# MCU036A_Target_Device.net
KiCad netlist of a schematic drawn in Altium Designer
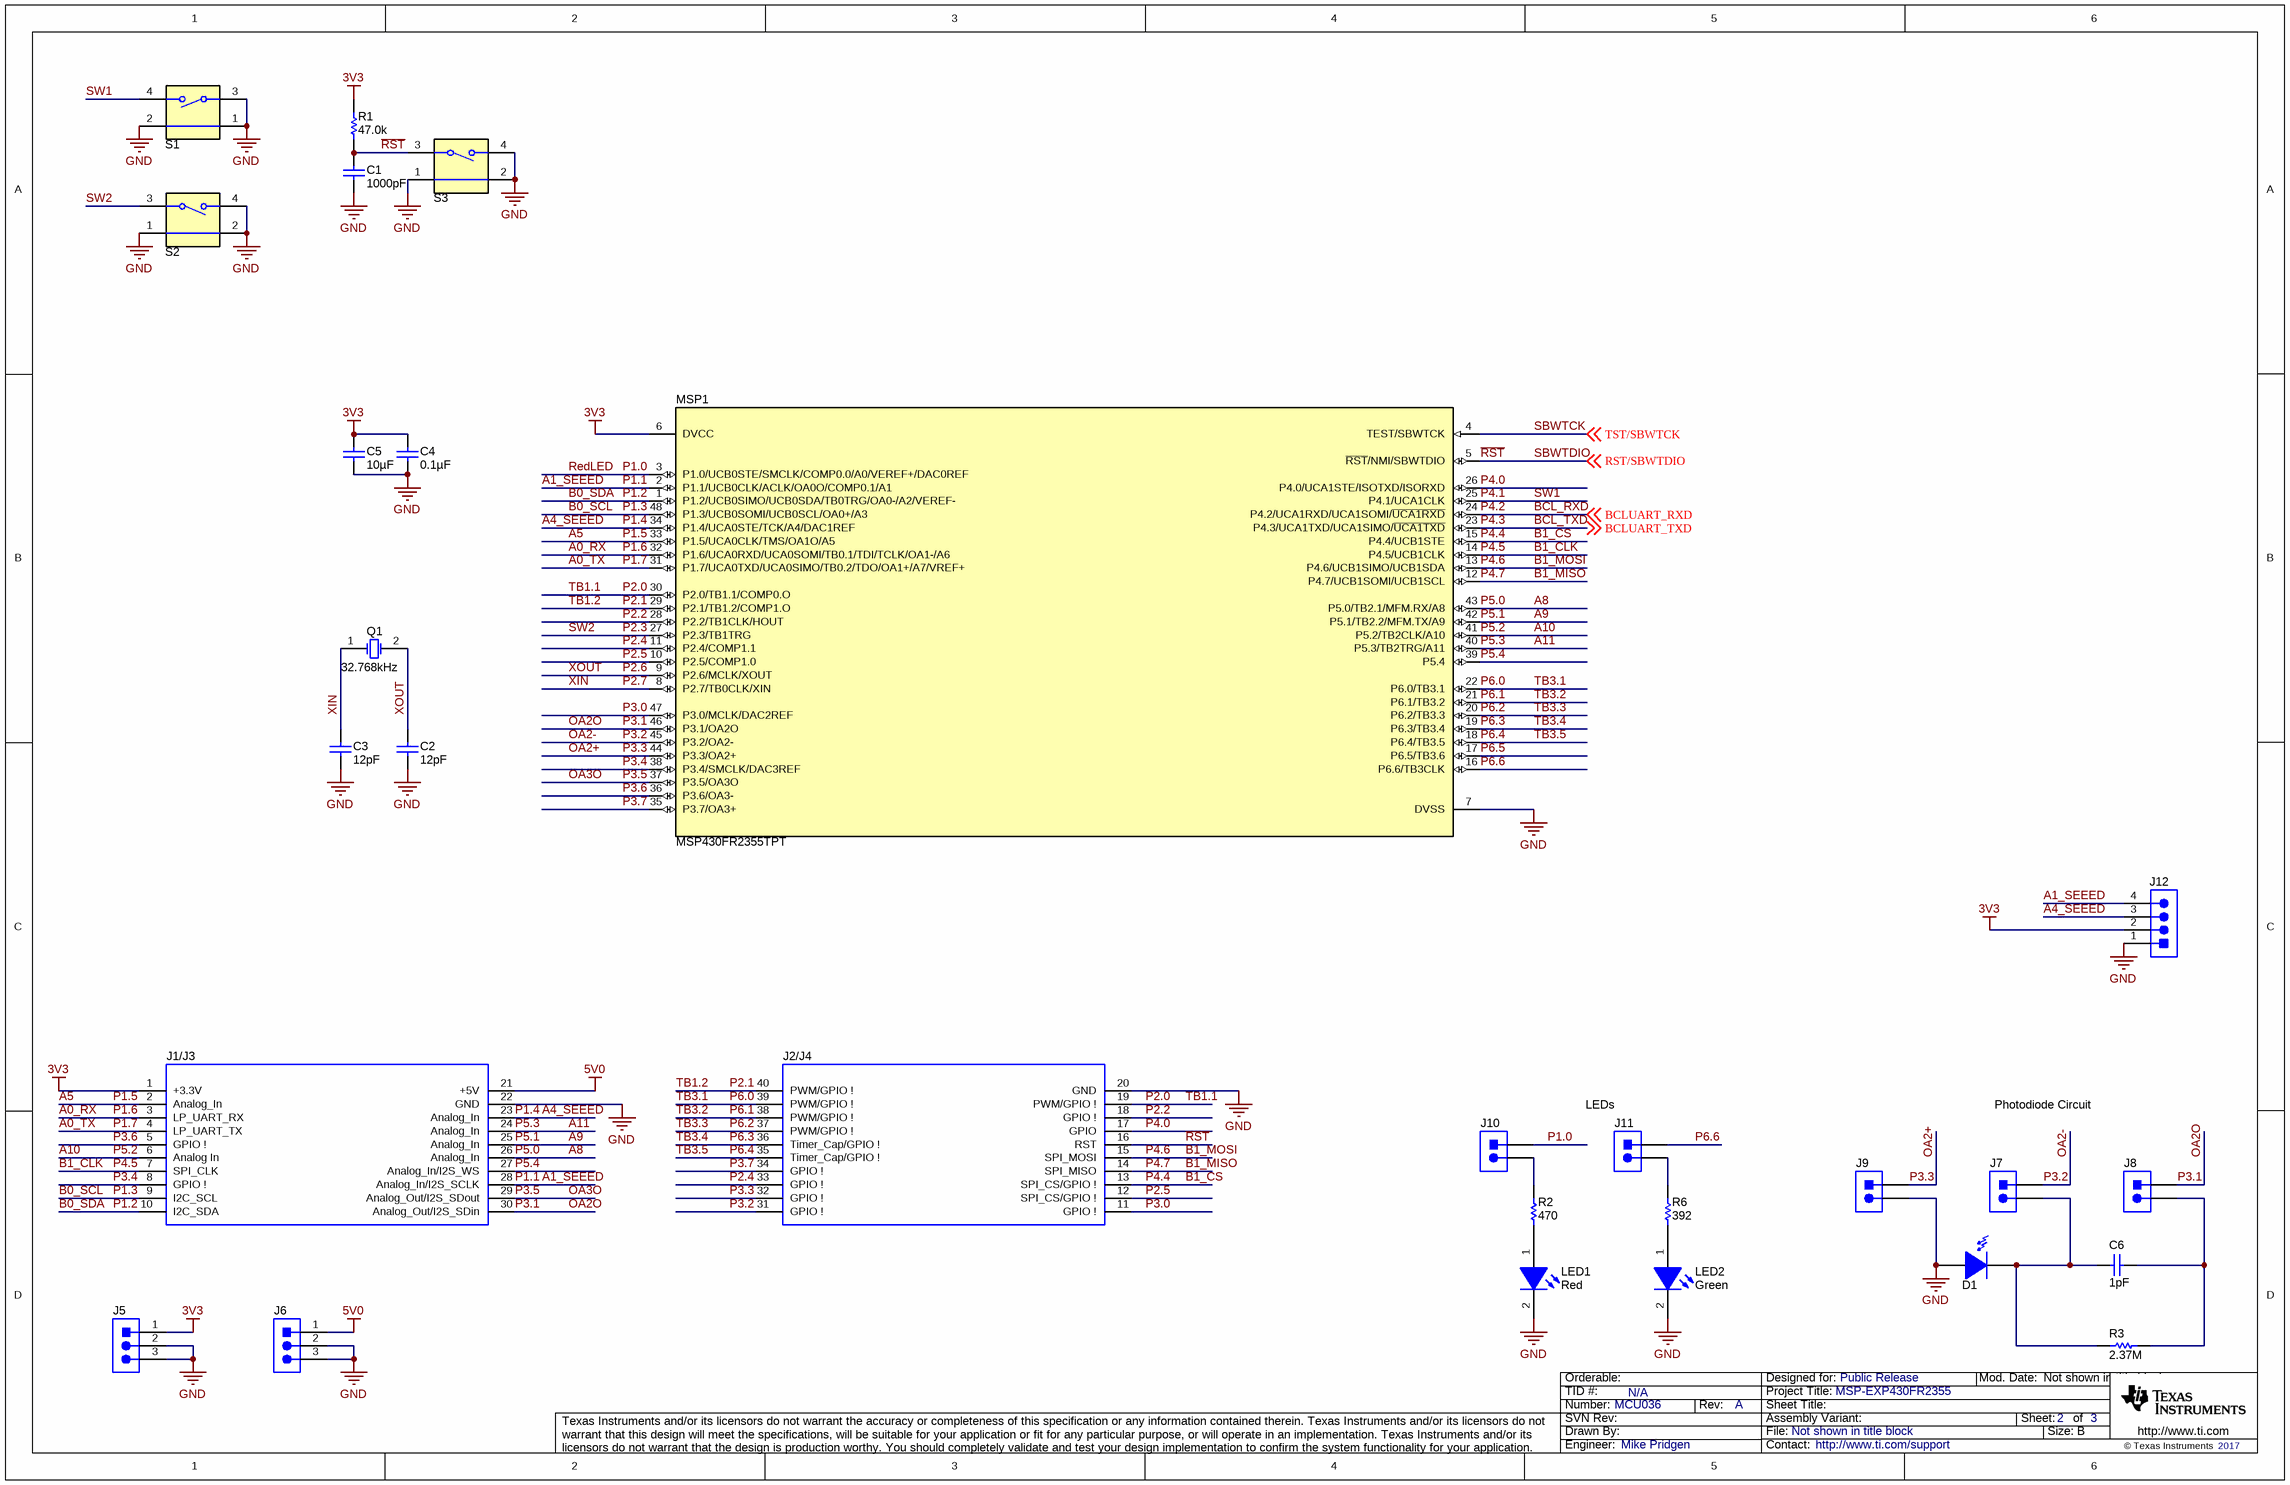
[diagram p0: MCU036A_Target_Device.SchDoc]

(export (version "E")
  (design (tool "Eeschema 10.0.6"))
  (components
    (comp (ref "C1")
      (value "GRM155R71H102KA01D")
      (footprint "0402")
      (description "CAP, CERM, 1000 pF, 50 V, +/- 10%, X7R, 0402")
      (fields
        (field (name "VALUEDISPLAYED") "1000pF")
        (field (name "MANUFACTURER") "MuRata")
        (field (name "PUBLISHER") "Texas Instruments")
      )
      (libsource (lib "Capacitor_Ceramic") (part "GRM155R71H102KA01D"))
    )
    (comp (ref "C2")
      (value "GRM1555C1E120JA01D")
      (footprint "0402")
      (description "CAP, CERM, 12 pF, 25 V, +/- 5%, C0G/NP0, 0402")
      (fields
        (field (name "VALUEDISPLAYED") "12pF")
        (field (name "MANUFACTURER") "MuRata")
        (field (name "PUBLISHER") "Texas Instruments")
      )
      (libsource (lib "Capacitor_Ceramic") (part "GRM1555C1E120JA01D"))
    )
    (comp (ref "C3")
      (value "GRM1555C1E120JA01D")
      (footprint "0402")
      (description "CAP, CERM, 12 pF, 25 V, +/- 5%, C0G/NP0, 0402")
      (fields
        (field (name "VALUEDISPLAYED") "12pF")
        (field (name "MANUFACTURER") "MuRata")
        (field (name "PUBLISHER") "Texas Instruments")
      )
      (libsource (lib "Capacitor_Ceramic") (part "GRM1555C1E120JA01D"))
    )
    (comp (ref "C4")
      (value "GRM155R61H104ME14D")
      (footprint "0402")
      (description "CAP, CERM, 0.1 µF, 50 V, +/- 20%, X5R, 0402")
      (fields
        (field (name "VALUEDISPLAYED") "0.1µF")
        (field (name "MANUFACTURER") "MuRata")
        (field (name "PUBLISHER") "Texas Instruments")
      )
      (libsource (lib "Capacitor_Ceramic") (part "GRM155R61H104ME14D"))
    )
    (comp (ref "C5")
      (value "GRM188R60J106ME84")
      (footprint "0603")
      (description "CAP, CERM, 10 µF, 6.3 V, +/- 20%, X5R, 0603")
      (fields
        (field (name "VALUEDISPLAYED") "10µF")
        (field (name "MANUFACTURER") "MuRata")
        (field (name "PUBLISHER") "Texas Instruments")
      )
      (libsource (lib "Capacitor_Ceramic") (part "GRM188R60J106ME84"))
    )
    (comp (ref "C6")
      (value "GRM1555C1H1R0BA01D")
      (footprint "0402")
      (description "CAP, CERM, 1 pF, 50 V, +/- 10%, C0G/NP0, 0402")
      (fields
        (field (name "VALUEDISPLAYED") "1pF")
        (field (name "MANUFACTURER") "MuRata")
        (field (name "PUBLISHER") "Texas Instruments")
      )
      (libsource (lib "Capacitor_Ceramic") (part "GRM1555C1H1R0BA01D"))
    )
    (comp (ref "D1")
      (value "SFH 2701")
      (footprint "SFH_2701")
      (description "High Speed PIN Photodiode, SMD")
      (fields (field (name "MANUFACTURER") "OSRAM"))
      (libsource (lib "Altium Vault - TI") (part "CMP-0002013-3"))
    )
    (comp (ref "J1/J3")
      (value "SSQ-110-03-T-D")
      (footprint "BoosterPack_40pin_J1J3")
      (description "Receptacle, 2.54mm, 10x2, Tin, TH")
      (fields
        (field (name "MANUFACTURER") "Samtec")
        (field (name "ALTERNATE PARTNUMBER") "CRD-081413-A-G")
        (field (name "SYMBOLCREATOR") "a0412235")
        (field (name "PUBLISHER") "Texas Instruments")
      )
      (libsource (lib "Hardware") (part "BoosterPack_40pin_J1J3"))
    )
    (comp (ref "J2/J4")
      (value "SSQ-110-03-T-D")
      (footprint "BoosterPack_40pin_J2J4")
      (description "Receptacle, 2.54mm, 10x2, Tin, TH")
      (fields
        (field (name "MANUFACTURER") "Samtec")
        (field (name "ALTERNATE PARTNUMBER") "CRD-081413-A-G")
        (field (name "SYMBOLCREATOR") "a0412235")
        (field (name "PUBLISHER") "Texas Instruments")
      )
      (libsource (lib "Hardware") (part "BoosterPack_40pin_J2J4"))
    )
    (comp (ref "J5")
      (value "PEC03SAAN")
      (footprint "PEC03SAAN_Launchpad_3V3")
      (description "Header, 100mil, 3x1, Tin, TH")
      (fields
        (field (name "MANUFACTURER") "Sullins Connector Solutions")
        (field (name "SYMBOLCREATOR") "a0799628")
        (field (name "PUBLISHER") "Texas Instruments")
      )
      (libsource (lib "Connectors_Sullins") (part "PEC03SAAN"))
    )
    (comp (ref "J6")
      (value "PEC03SAAN")
      (footprint "PEC03SAAN_Launchpad_5V0")
      (description "Header, 100mil, 3x1, Tin, TH")
      (fields
        (field (name "MANUFACTURER") "Sullins Connector Solutions")
        (field (name "SYMBOLCREATOR") "a0799628")
        (field (name "PUBLISHER") "Texas Instruments")
      )
      (libsource (lib "Connectors_Sullins") (part "PEC03SAAN"))
    )
    (comp (ref "J7")
      (value "TSW-102-07-G-S")
      (footprint "TSW-102-07-G-S")
      (description "Header, 100mil, 2x1, Gold, TH")
      (fields
        (field (name "MANUFACTURER") "Samtec")
        (field (name "SYMBOLCREATOR") "a0412235")
        (field (name "PUBLISHER") "Texas Instruments")
      )
      (libsource (lib "Connectors_Samtec") (part "TSW-102-07-G-S"))
    )
    (comp (ref "J8")
      (value "TSW-102-07-G-S")
      (footprint "TSW-102-07-G-S")
      (description "Header, 100mil, 2x1, Gold, TH")
      (fields
        (field (name "MANUFACTURER") "Samtec")
        (field (name "SYMBOLCREATOR") "a0412235")
        (field (name "PUBLISHER") "Texas Instruments")
      )
      (libsource (lib "Connectors_Samtec") (part "TSW-102-07-G-S"))
    )
    (comp (ref "J9")
      (value "TSW-102-07-G-S")
      (footprint "TSW-102-07-G-S")
      (description "Header, 100mil, 2x1, Gold, TH")
      (fields
        (field (name "MANUFACTURER") "Samtec")
        (field (name "SYMBOLCREATOR") "a0412235")
        (field (name "PUBLISHER") "Texas Instruments")
      )
      (libsource (lib "Connectors_Samtec") (part "TSW-102-07-G-S"))
    )
    (comp (ref "J10")
      (value "TSW-102-07-G-S")
      (footprint "TSW-102-07-G-S")
      (description "Header, 100mil, 2x1, Gold, TH")
      (fields
        (field (name "MANUFACTURER") "Samtec")
        (field (name "SYMBOLCREATOR") "a0412235")
        (field (name "PUBLISHER") "Texas Instruments")
      )
      (libsource (lib "Connectors_Samtec") (part "TSW-102-07-G-S"))
    )
    (comp (ref "J11")
      (value "TSW-102-07-G-S")
      (footprint "TSW-102-07-G-S")
      (description "Header, 100mil, 2x1, Gold, TH")
      (fields
        (field (name "MANUFACTURER") "Samtec")
        (field (name "SYMBOLCREATOR") "a0412235")
        (field (name "PUBLISHER") "Texas Instruments")
      )
      (libsource (lib "Connectors_Samtec") (part "TSW-102-07-G-S"))
    )
    (comp (ref "J12")
      (value "110990037")
      (footprint "SEEED_110990037")
      (description "Header(shrouded), 2mm, 4x1, Tin, R/A, TH")
      (fields
        (field (name "MANUFACTURER") "SEEED")
        (field (name "SYMBOLCREATOR") "a0412235")
        (field (name "PUBLISHER") "Texas Instruments")
      )
      (libsource (lib "Connectors_Other") (part "110990037"))
    )
    (comp (ref "LED1")
      (value "Red")
      (footprint "LED_LTST-C190_Red")
      (description "LED, Red, SMD")
      (fields
        (field (name "PARTNUMBER") "LTST-C190CKT")
        (field (name "MANUFACTURER") "Lite-On")
        (field (name "PUBLISHER") "Texas Instruments")
      )
      (libsource (lib "LED") (part "LTST-C190CKT"))
    )
    (comp (ref "LED2")
      (value "Green")
      (footprint "LED_LTST-C190")
      (description "LED, Green, SMD")
      (fields
        (field (name "PARTNUMBER") "LTST-C190GKT")
        (field (name "MANUFACTURER") "Lite-On")
        (field (name "PUBLISHER") "Texas Instruments")
      )
      (libsource (lib "LED") (part "LTST-C190GKT"))
    )
    (comp (ref "MSP1")
      (value "MSP430FR2355TPT")
      (footprint "PT0048A_N")
      (description "Mixed-Signal Microcontroller, PT0048A (LQFP-48)")
      (fields
        (field (name "ALTERNATE PARTNUMBER") "XMS430FR2355TPT")
        (field (name "MANUFACTURER") "Texas Instruments")
        (field (name "SYMBOLCREATOR") "Altium")
        (field (name "PUBLISHER") "Texas Instruments")
      )
      (libsource (lib "TI_Pre_RTM") (part "MSP430FR2355IPT"))
    )
    (comp (ref "Q1")
      (value "ECS-.327-12.5-34B-TR")
      (footprint "Epson_FC-135")
      (description "Crystal, 32.768 KHz, 12.5 pF, SMD")
      (fields
        (field (name "FREQUENCY") "32.768kHz")
        (field (name "MANUFACTURER") "ECS Inc.")
        (field (name "SYMBOLCREATOR") "a0412235")
        (field (name "PUBLISHER") "Texas Instruments")
      )
      (libsource (lib "Oscillators") (part "X1A0001410014"))
    )
    (comp (ref "R1")
      (value "RC0402FR-0747KL")
      (footprint "0402")
      (description "RES, 47.0 k, 1%, 0.0625 W, 0402")
      (fields
        (field (name "VALUEDISPLAYED") "47.0k")
        (field (name "MANUFACTURER") "Yageo America")
        (field (name "PUBLISHER") "Texas Instruments")
      )
      (libsource (lib "Resistor_0402") (part "RC0402FR-0747KL"))
    )
    (comp (ref "R2")
      (value "RC0402FR-07470RL")
      (footprint "0402")
      (description "RES, 470, 1%, 0.063 W, 0402")
      (fields
        (field (name "VALUEDISPLAYED") "470")
        (field (name "MANUFACTURER") "Yageo America")
        (field (name "PUBLISHER") "Texas Instruments")
      )
      (libsource (lib "Resistor_0402") (part "RC0402FR-07470RL"))
    )
    (comp (ref "R3")
      (value "CRCW06032M37FKEA")
      (footprint "0603")
      (description "RES, 2.37 M, 1%, 0.1 W, 0603")
      (fields
        (field (name "VALUEDISPLAYED") "2.37M")
        (field (name "MANUFACTURER") "Vishay-Dale")
        (field (name "PUBLISHER") "Texas Instruments")
      )
      (libsource (lib "Resistor_0603") (part "CRCW06032M37FKEA"))
    )
    (comp (ref "R6")
      (value "CRCW0402392RFKED")
      (footprint "0402")
      (description "RES, 392, 1%, 0.063 W, 0402")
      (fields
        (field (name "VALUEDISPLAYED") "392")
        (field (name "MANUFACTURER") "Vishay-Dale")
        (field (name "PUBLISHER") "Texas Instruments")
      )
      (libsource (lib "Resistor_0402") (part "CRCW0402392RFKED"))
    )
    (comp (ref "S1")
      (value "1188E-1K2-V-TR")
      (footprint "SW_1188E")
      (description "Switch, SPST, 0.05 A, 12 VDC, SMD")
      (fields
        (field (name "MANUFACTURER") "Diptronics")
        (field (name "SYMBOLCREATOR") "Altium")
        (field (name "PUBLISHER") "Texas Instruments")
      )
      (libsource (lib "") (part "1188E-1K2-V-TR_1"))
    )
    (comp (ref "S2")
      (value "1188E-1K2-V-TR")
      (footprint "SW_1188E")
      (description "Switch, SPST, 0.05 A, 12 VDC, SMD")
      (fields
        (field (name "MANUFACTURER") "Diptronics")
        (field (name "SYMBOLCREATOR") "Altium")
        (field (name "PUBLISHER") "Texas Instruments")
      )
      (libsource (lib "Switches") (part "1188E-1K2-V-TR"))
    )
    (comp (ref "S3")
      (value "1188E-1K2-V-TR")
      (footprint "SW_1188E")
      (description "Switch, SPST, 0.05 A, 12 VDC, SMD")
      (fields
        (field (name "MANUFACTURER") "Diptronics")
        (field (name "SYMBOLCREATOR") "Altium")
        (field (name "PUBLISHER") "Texas Instruments")
      )
      (libsource (lib "Switches") (part "1188E-1K2-V-TR"))
    )
  )
  (nets
    (net (code "1") (name "/A0_RX") (class "Default")
      (node (ref "J1/J3") (pin "3") (pinfunction "LP_UART_RX_3") (pintype "passive"))
      (node (ref "MSP1") (pin "32") (pinfunction "P1.6/UCA0RXD/UCA0SOMI/TB0.1/TDI/TCLK/OA1-/A6_32") (pintype "bidirectional"))
    )
    (net (code "2") (name "/A0_TX") (class "Default")
      (node (ref "J1/J3") (pin "4") (pinfunction "LP_UART_TX_4") (pintype "passive"))
      (node (ref "MSP1") (pin "31") (pinfunction "P1.7/UCA0TXD/UCA0SIMO/TB0.2/TDO/OA1+/A7/VREF+_31") (pintype "bidirectional"))
    )
    (net (code "3") (name "/A1_SEEED") (class "Default")
      (node (ref "J1/J3") (pin "28") (pinfunction "Analog_In/I2S_SCLK_28") (pintype "passive"))
      (node (ref "J12") (pin "4") (pinfunction "4_4") (pintype "passive"))
      (node (ref "MSP1") (pin "2") (pinfunction "P1.1/UCB0CLK/ACLK/OA0O/COMP0.1/A1_2") (pintype "bidirectional"))
    )
    (net (code "4") (name "/A4_SEEED") (class "Default")
      (node (ref "J1/J3") (pin "23") (pinfunction "Analog_In_23") (pintype "passive"))
      (node (ref "J12") (pin "3") (pinfunction "3_3") (pintype "passive"))
      (node (ref "MSP1") (pin "34") (pinfunction "P1.4/UCA0STE/TCK/A4/DAC1REF_34") (pintype "bidirectional"))
    )
    (net (code "5") (name "/A5") (class "Default")
      (node (ref "J1/J3") (pin "2") (pinfunction "Analog_In_2") (pintype "passive"))
      (node (ref "MSP1") (pin "33") (pinfunction "P1.5/UCA0CLK/TMS/OA1O/A5_33") (pintype "bidirectional"))
    )
    (net (code "6") (name "/A8") (class "Default")
      (node (ref "J1/J3") (pin "26") (pinfunction "Analog_In_26") (pintype "passive"))
      (node (ref "MSP1") (pin "43") (pinfunction "P5.0/TB2.1/MFM.RX/A8_43") (pintype "bidirectional"))
    )
    (net (code "7") (name "/A9") (class "Default")
      (node (ref "J1/J3") (pin "25") (pinfunction "Analog_In_25") (pintype "passive"))
      (node (ref "MSP1") (pin "42") (pinfunction "P5.1/TB2.2/MFM.TX/A9_42") (pintype "bidirectional"))
    )
    (net (code "8") (name "/A10") (class "Default")
      (node (ref "J1/J3") (pin "6") (pinfunction "Analog_In_6") (pintype "passive"))
      (node (ref "MSP1") (pin "41") (pinfunction "P5.2/TB2CLK/A10_41") (pintype "bidirectional"))
    )
    (net (code "9") (name "/A11") (class "Default")
      (node (ref "J1/J3") (pin "24") (pinfunction "Analog_In_24") (pintype "passive"))
      (node (ref "MSP1") (pin "40") (pinfunction "P5.3/TB2TRG/A11_40") (pintype "bidirectional"))
    )
    (net (code "10") (name "/B0_SCL") (class "Default")
      (node (ref "J1/J3") (pin "9") (pinfunction "I2C_SCL_9") (pintype "passive"))
      (node (ref "MSP1") (pin "48") (pinfunction "P1.3/UCB0SOMI/UCB0SCL/OA0+/A3_48") (pintype "bidirectional"))
    )
    (net (code "11") (name "/B0_SDA") (class "Default")
      (node (ref "J1/J3") (pin "10") (pinfunction "I2C_SDA_10") (pintype "passive"))
      (node (ref "MSP1") (pin "1") (pinfunction "P1.2/UCB0SIMO/UCB0SDA/TB0TRG/OA0-/A2/VEREF-_1") (pintype "bidirectional"))
    )
    (net (code "12") (name "/B1_CLK") (class "Default")
      (node (ref "J1/J3") (pin "7") (pinfunction "SPI_CLK_7") (pintype "passive"))
      (node (ref "MSP1") (pin "14") (pinfunction "P4.5/UCB1CLK_14") (pintype "bidirectional"))
    )
    (net (code "13") (name "/B1_CS") (class "Default")
      (node (ref "J2/J4") (pin "13") (pinfunction "SPI_CS/GPIO_!_13") (pintype "passive"))
      (node (ref "MSP1") (pin "15") (pinfunction "P4.4/UCB1STE_15") (pintype "bidirectional"))
    )
    (net (code "14") (name "/B1_MISO") (class "Default")
      (node (ref "J2/J4") (pin "14") (pinfunction "SPI_MISO_14") (pintype "passive"))
      (node (ref "MSP1") (pin "12") (pinfunction "P4.7/UCB1SOMI/UCB1SCL_12") (pintype "bidirectional"))
    )
    (net (code "15") (name "/B1_MOSI") (class "Default")
      (node (ref "J2/J4") (pin "15") (pinfunction "SPI_MOSI_15") (pintype "passive"))
      (node (ref "MSP1") (pin "13") (pinfunction "P4.6/UCB1SIMO/UCB1SDA_13") (pintype "bidirectional"))
    )
    (net (code "16") (name "/OA2+") (class "Default")
      (node (ref "J2/J4") (pin "32") (pinfunction "GPIO_!_32") (pintype "passive"))
      (node (ref "J9") (pin "1") (pinfunction "1_1") (pintype "passive"))
      (node (ref "MSP1") (pin "44") (pinfunction "P3.3/OA2+_44") (pintype "bidirectional"))
    )
    (net (code "17") (name "/OA2-") (class "Default")
      (node (ref "J2/J4") (pin "31") (pinfunction "GPIO_!_31") (pintype "passive"))
      (node (ref "J7") (pin "1") (pinfunction "1_1") (pintype "passive"))
      (node (ref "MSP1") (pin "45") (pinfunction "P3.2/OA2-_45") (pintype "bidirectional"))
    )
    (net (code "18") (name "/OA2O") (class "Default")
      (node (ref "J1/J3") (pin "30") (pinfunction "Analog_Out/I2S_SDin_30") (pintype "passive"))
      (node (ref "J8") (pin "1") (pinfunction "1_1") (pintype "passive"))
      (node (ref "MSP1") (pin "46") (pinfunction "P3.1/OA2O_46") (pintype "bidirectional"))
    )
    (net (code "19") (name "/OA3O") (class "Default")
      (node (ref "J1/J3") (pin "29") (pinfunction "Analog_Out/I2S_SDout_29") (pintype "passive"))
      (node (ref "MSP1") (pin "37") (pinfunction "P3.5/OA3O_37") (pintype "bidirectional"))
    )
    (net (code "20") (name "/P1.0") (class "Default")
      (node (ref "J10") (pin "1") (pinfunction "1_1") (pintype "passive"))
      (node (ref "MSP1") (pin "3") (pinfunction "P1.0/UCB0STE/SMCLK/COMP0.0/A0/VEREF+/DAC0REF_3") (pintype "bidirectional"))
    )
    (net (code "21") (name "/P2.0") (class "Default")
      (node (ref "J2/J4") (pin "19") (pinfunction "PWM/GPIO_!_19") (pintype "passive"))
      (node (ref "MSP1") (pin "30") (pinfunction "P2.0/TB1.1/COMP0.O_30") (pintype "bidirectional"))
    )
    (net (code "22") (name "/P2.1") (class "Default")
      (node (ref "J2/J4") (pin "40") (pinfunction "PWM/GPIO_!_40") (pintype "passive"))
      (node (ref "MSP1") (pin "29") (pinfunction "P2.1/TB1.2/COMP1.O_29") (pintype "bidirectional"))
    )
    (net (code "23") (name "/P2.2") (class "Default")
      (node (ref "J2/J4") (pin "18") (pinfunction "GPIO_!_18") (pintype "passive"))
      (node (ref "MSP1") (pin "28") (pinfunction "P2.2/TB1CLK/HOUT_28") (pintype "bidirectional"))
    )
    (net (code "24") (name "/P2.3") (class "Default")
      (node (ref "MSP1") (pin "27") (pinfunction "P2.3/TB1TRG_27") (pintype "bidirectional"))
      (node (ref "S2") (pin "3") (pinfunction "3_3") (pintype "passive"))
    )
    (net (code "25") (name "/P2.4") (class "Default")
      (node (ref "J2/J4") (pin "33") (pinfunction "GPIO_!_33") (pintype "passive"))
      (node (ref "MSP1") (pin "11") (pinfunction "P2.4/COMP1.1_11") (pintype "bidirectional"))
    )
    (net (code "26") (name "/P2.5") (class "Default")
      (node (ref "J2/J4") (pin "12") (pinfunction "SPI_CS/GPIO_!_12") (pintype "passive"))
      (node (ref "MSP1") (pin "10") (pinfunction "P2.5/COMP1.0_10") (pintype "bidirectional"))
    )
    (net (code "27") (name "/P2.6") (class "Default")
      (node (ref "C2") (pin "1") (pinfunction "1_1") (pintype "passive"))
      (node (ref "MSP1") (pin "9") (pinfunction "P2.6/MCLK/XOUT_9") (pintype "bidirectional"))
      (node (ref "Q1") (pin "2") (pinfunction "OSC2_2") (pintype "passive"))
    )
    (net (code "28") (name "/P2.7") (class "Default")
      (node (ref "C3") (pin "1") (pinfunction "1_1") (pintype "passive"))
      (node (ref "MSP1") (pin "8") (pinfunction "P2.7/TB0CLK/XIN_8") (pintype "bidirectional"))
      (node (ref "Q1") (pin "1") (pinfunction "OSC1_1") (pintype "passive"))
    )
    (net (code "29") (name "/P3.0") (class "Default")
      (node (ref "J2/J4") (pin "11") (pinfunction "GPIO_!_11") (pintype "passive"))
      (node (ref "MSP1") (pin "47") (pinfunction "P3.0/MCLK/DAC2REF_47") (pintype "bidirectional"))
    )
    (net (code "30") (name "/P3.4") (class "Default")
      (node (ref "J1/J3") (pin "8") (pinfunction "GPIO_!_8") (pintype "passive"))
      (node (ref "MSP1") (pin "38") (pinfunction "P3.4/SMCLK/DAC3REF_38") (pintype "bidirectional"))
    )
    (net (code "31") (name "/P3.6") (class "Default")
      (node (ref "J1/J3") (pin "5") (pinfunction "GPIO_!_5") (pintype "passive"))
      (node (ref "MSP1") (pin "36") (pinfunction "P3.6/OA3-_36") (pintype "bidirectional"))
    )
    (net (code "32") (name "/P3.7") (class "Default")
      (node (ref "J2/J4") (pin "34") (pinfunction "GPIO_!_34") (pintype "passive"))
      (node (ref "MSP1") (pin "35") (pinfunction "P3.7/OA3+_35") (pintype "bidirectional"))
    )
    (net (code "33") (name "/P4.0") (class "Default")
      (node (ref "J2/J4") (pin "17") (pinfunction "GPIO_17") (pintype "passive"))
      (node (ref "MSP1") (pin "26") (pinfunction "P4.0/UCA1STE/ISOTXD/ISORXD_26") (pintype "bidirectional"))
    )
    (net (code "34") (name "/P4.1") (class "Default")
      (node (ref "MSP1") (pin "25") (pinfunction "P4.1/UCA1CLK_25") (pintype "bidirectional"))
      (node (ref "S1") (pin "4") (pinfunction "4_4") (pintype "passive"))
    )
    (net (code "35") (name "/P5.4") (class "Default")
      (node (ref "J1/J3") (pin "27") (pinfunction "Analog_In/I2S_WS_27") (pintype "passive"))
      (node (ref "MSP1") (pin "39") (pinfunction "P5.4_39") (pintype "bidirectional"))
    )
    (net (code "36") (name "/P6.0") (class "Default")
      (node (ref "J2/J4") (pin "39") (pinfunction "PWM/GPIO_!_39") (pintype "passive"))
      (node (ref "MSP1") (pin "22") (pinfunction "P6.0/TB3.1_22") (pintype "bidirectional"))
    )
    (net (code "37") (name "/P6.1") (class "Default")
      (node (ref "J2/J4") (pin "38") (pinfunction "PWM/GPIO_!_38") (pintype "passive"))
      (node (ref "MSP1") (pin "21") (pinfunction "P6.1/TB3.2_21") (pintype "bidirectional"))
    )
    (net (code "38") (name "/P6.2") (class "Default")
      (node (ref "J2/J4") (pin "37") (pinfunction "PWM/GPIO_!_37") (pintype "passive"))
      (node (ref "MSP1") (pin "20") (pinfunction "P6.2/TB3.3_20") (pintype "bidirectional"))
    )
    (net (code "39") (name "/P6.3") (class "Default")
      (node (ref "J2/J4") (pin "36") (pinfunction "Timer_Cap/GPIO_!_36") (pintype "passive"))
      (node (ref "MSP1") (pin "19") (pinfunction "P6.3/TB3.4_19") (pintype "bidirectional"))
    )
    (net (code "40") (name "/P6.4") (class "Default")
      (node (ref "J2/J4") (pin "35") (pinfunction "Timer_Cap/GPIO_!_35") (pintype "passive"))
      (node (ref "MSP1") (pin "18") (pinfunction "P6.4/TB3.5_18") (pintype "bidirectional"))
    )
    (net (code "41") (name "/P6.5") (class "Default")
      (node (ref "MSP1") (pin "17") (pinfunction "P6.5/TB3.6_17") (pintype "bidirectional"))
    )
    (net (code "42") (name "/P6.6") (class "Default")
      (node (ref "J11") (pin "1") (pinfunction "1_1") (pintype "passive"))
      (node (ref "MSP1") (pin "16") (pinfunction "P6.6/TB3CLK_16") (pintype "bidirectional"))
    )
    (net (code "43") (name "3V3") (class "Default")
      (node (ref "C4") (pin "1") (pinfunction "1_1") (pintype "passive"))
      (node (ref "C5") (pin "2") (pinfunction "2_2") (pintype "passive"))
      (node (ref "J1/J3") (pin "1") (pinfunction "+3.3V_1") (pintype "power_in"))
      (node (ref "J12") (pin "2") (pinfunction "2_2") (pintype "passive"))
      (node (ref "J5") (pin "1") (pinfunction "1_1") (pintype "passive"))
      (node (ref "MSP1") (pin "6") (pinfunction "DVCC_6") (pintype "power_in"))
      (node (ref "R1") (pin "2") (pinfunction "2_2") (pintype "passive"))
    )
    (net (code "44") (name "5V0") (class "Default")
      (node (ref "J1/J3") (pin "21") (pinfunction "+5V_21") (pintype "power_in"))
      (node (ref "J6") (pin "1") (pinfunction "1_1") (pintype "passive"))
    )
    (net (code "45") (name "BCLUART_RXD") (class "Default")
      (node (ref "MSP1") (pin "24") (pinfunction "P4.2/UCA1RXD/UCA1SOMI/~{UCA1RXD}_24") (pintype "bidirectional"))
    )
    (net (code "46") (name "BCLUART_TXD") (class "Default")
      (node (ref "MSP1") (pin "23") (pinfunction "P4.3/UCA1TXD/UCA1SIMO/~{UCA1TXD}_23") (pintype "bidirectional"))
    )
    (net (code "47") (name "GND") (class "Default")
      (node (ref "C1") (pin "2") (pinfunction "2_2") (pintype "passive"))
      (node (ref "C2") (pin "2") (pinfunction "2_2") (pintype "passive"))
      (node (ref "C3") (pin "2") (pinfunction "2_2") (pintype "passive"))
      (node (ref "C4") (pin "2") (pinfunction "2_2") (pintype "passive"))
      (node (ref "C5") (pin "1") (pinfunction "1_1") (pintype "passive"))
      (node (ref "D1") (pin "2") (pinfunction "A_2") (pintype "passive"))
      (node (ref "J1/J3") (pin "22") (pinfunction "GND_22") (pintype "power_in"))
      (node (ref "J12") (pin "1") (pinfunction "1_1") (pintype "passive"))
      (node (ref "J2/J4") (pin "20") (pinfunction "GND_20") (pintype "power_in"))
      (node (ref "J5") (pin "2") (pinfunction "2_2") (pintype "passive"))
      (node (ref "J5") (pin "3") (pinfunction "3_3") (pintype "passive"))
      (node (ref "J6") (pin "2") (pinfunction "2_2") (pintype "passive"))
      (node (ref "J6") (pin "3") (pinfunction "3_3") (pintype "passive"))
      (node (ref "J9") (pin "2") (pinfunction "2_2") (pintype "passive"))
      (node (ref "LED1") (pin "2") (pinfunction "K_2") (pintype "passive"))
      (node (ref "LED2") (pin "2") (pinfunction "K_2") (pintype "passive"))
      (node (ref "MSP1") (pin "7") (pinfunction "DVSS_7") (pintype "power_in"))
      (node (ref "S1") (pin "1") (pinfunction "1_1") (pintype "passive"))
      (node (ref "S1") (pin "2") (pinfunction "2_2") (pintype "passive"))
      (node (ref "S1") (pin "3") (pinfunction "3_3") (pintype "passive"))
      (node (ref "S2") (pin "1") (pinfunction "1_1") (pintype "passive"))
      (node (ref "S2") (pin "2") (pinfunction "2_2") (pintype "passive"))
      (node (ref "S2") (pin "4") (pinfunction "4_4") (pintype "passive"))
      (node (ref "S3") (pin "1") (pinfunction "1_1") (pintype "passive"))
      (node (ref "S3") (pin "2") (pinfunction "2_2") (pintype "passive"))
      (node (ref "S3") (pin "4") (pinfunction "4_4") (pintype "passive"))
    )
    (net (code "48") (name "Net-(C6-Pad1)") (class "Default")
      (node (ref "C6") (pin "1") (pinfunction "1_1") (pintype "passive"))
      (node (ref "J8") (pin "2") (pinfunction "2_2") (pintype "passive"))
      (node (ref "R3") (pin "2") (pinfunction "2_2") (pintype "passive"))
    )
    (net (code "49") (name "Net-(D1-C)") (class "Default")
      (node (ref "C6") (pin "2") (pinfunction "2_2") (pintype "passive"))
      (node (ref "D1") (pin "1") (pinfunction "C_1") (pintype "passive"))
      (node (ref "J7") (pin "2") (pinfunction "2_2") (pintype "passive"))
      (node (ref "R3") (pin "1") (pinfunction "1_1") (pintype "passive"))
    )
    (net (code "50") (name "Net-(J10-Pad2)") (class "Default")
      (node (ref "J10") (pin "2") (pinfunction "2_2") (pintype "passive"))
      (node (ref "R2") (pin "2") (pinfunction "2_2") (pintype "passive"))
    )
    (net (code "51") (name "Net-(J11-Pad2)") (class "Default")
      (node (ref "J11") (pin "2") (pinfunction "2_2") (pintype "passive"))
      (node (ref "R6") (pin "2") (pinfunction "2_2") (pintype "passive"))
    )
    (net (code "52") (name "Net-(LED1-A)") (class "Default")
      (node (ref "LED1") (pin "1") (pinfunction "A_1") (pintype "passive"))
      (node (ref "R2") (pin "1") (pinfunction "1_1") (pintype "passive"))
    )
    (net (code "53") (name "Net-(LED2-A)") (class "Default")
      (node (ref "LED2") (pin "1") (pinfunction "A_1") (pintype "passive"))
      (node (ref "R6") (pin "1") (pinfunction "1_1") (pintype "passive"))
    )
    (net (code "54") (name "RST{slash}SBWTDIO") (class "Default")
      (node (ref "C1") (pin "1") (pinfunction "1_1") (pintype "passive"))
      (node (ref "J2/J4") (pin "16") (pinfunction "RST_16") (pintype "passive"))
      (node (ref "MSP1") (pin "5") (pinfunction "~{RST}/NMI/SBWTDIO_5") (pintype "bidirectional"))
      (node (ref "R1") (pin "1") (pinfunction "1_1") (pintype "passive"))
      (node (ref "S3") (pin "3") (pinfunction "3_3") (pintype "passive"))
    )
    (net (code "55") (name "TST{slash}SBWTCK") (class "Default")
      (node (ref "MSP1") (pin "4") (pinfunction "TEST/SBWTCK_4") (pintype "input"))
    )
  )
)
